# ADXL362WakeOnShake.net
KiCad netlist of a schematic drawn in EAGLE
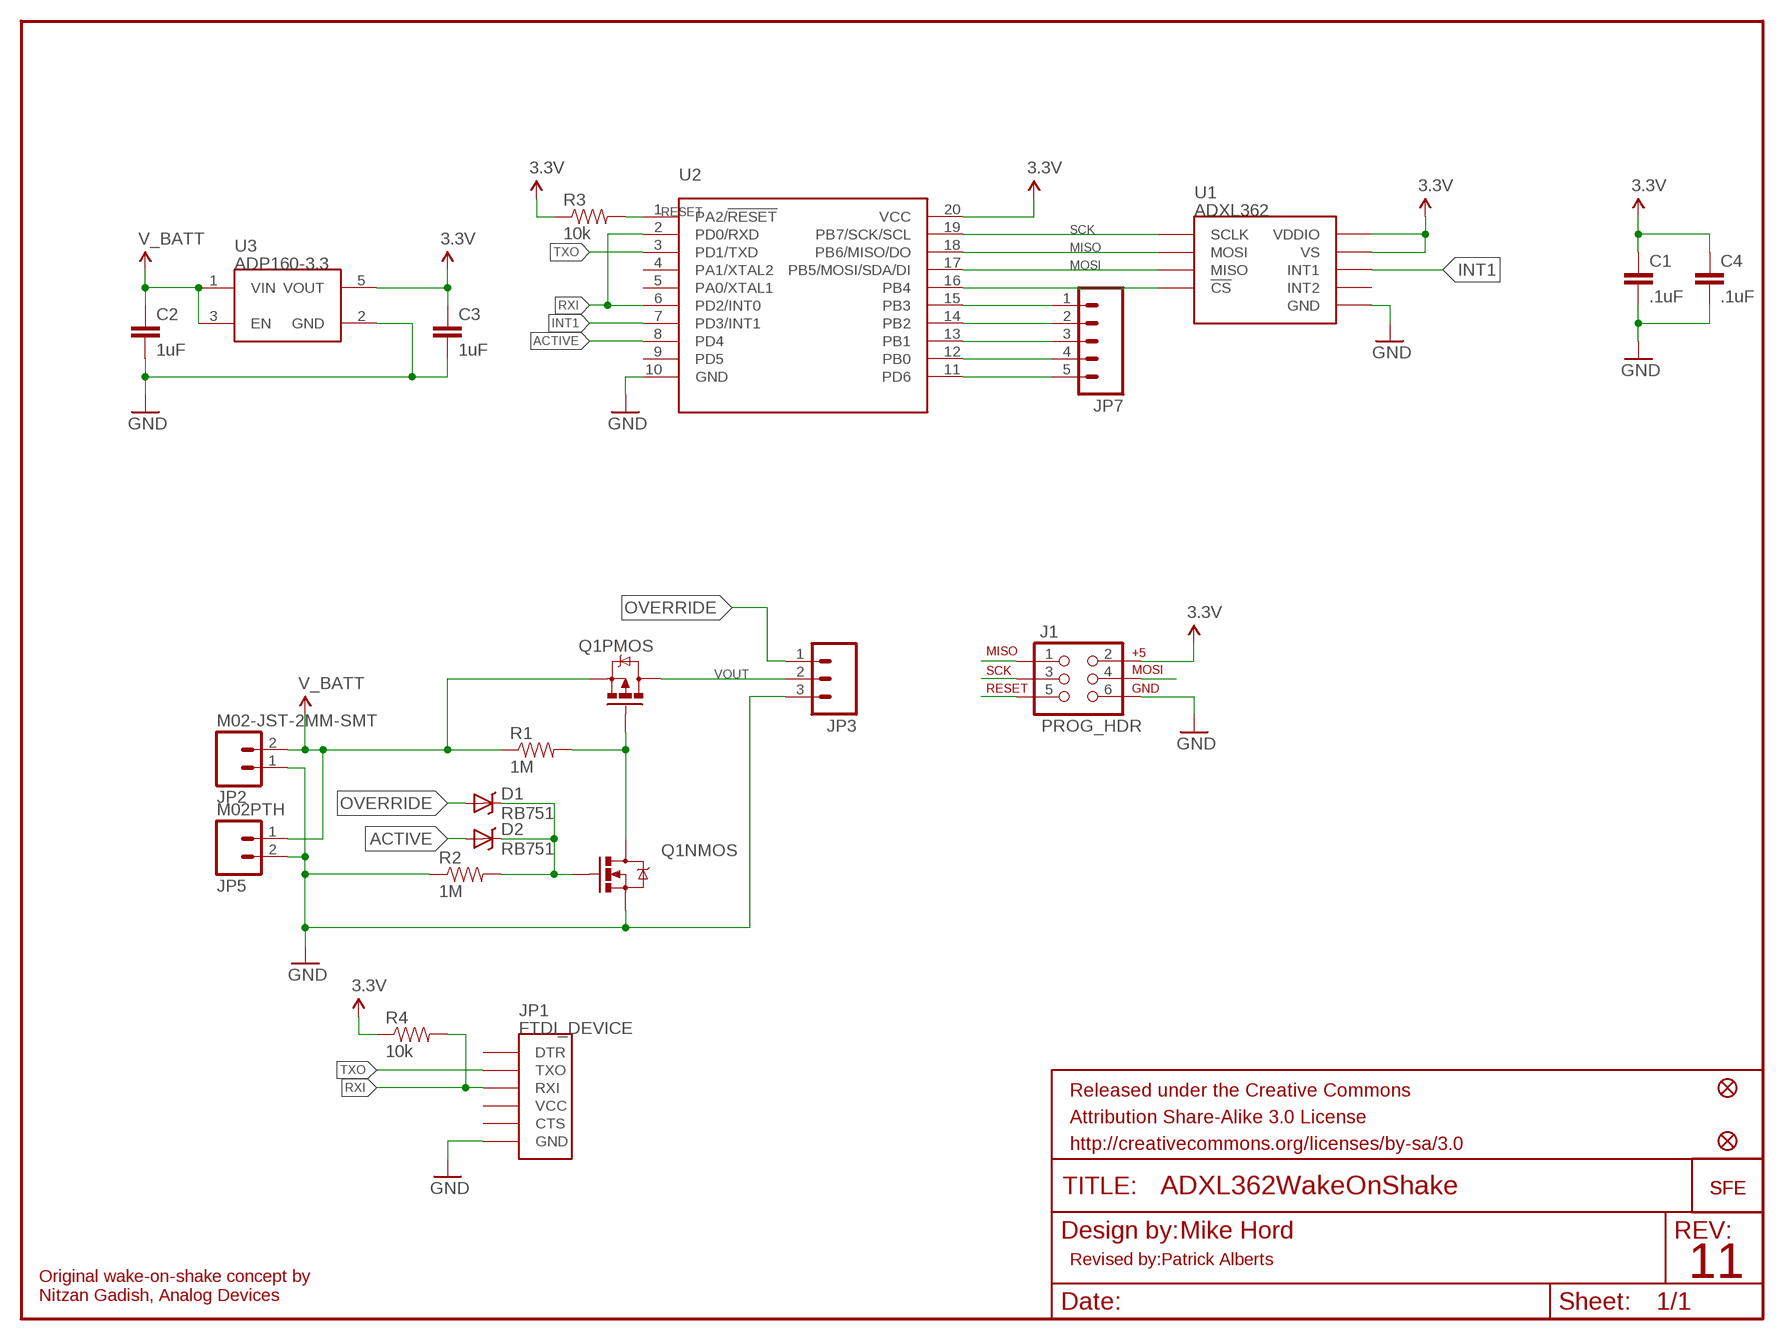
[diagram p0: schematic, sheet 1]

(export (version "E")
  (design (tool "Eeschema 10.0.6"))
  (components
    (comp (ref "C1")
      (value ".1uF")
      (footprint "eagle-import:0603-CAP")
      (fields (field (name "PROD_ID") "CAP-00810"))
      (libsource (lib "eagle-import") (part "0.1UF-25V(+80/-20%)(0603)"))
    )
    (comp (ref "C2")
      (value "1uF")
      (footprint "eagle-import:0603-CAP")
      (fields (field (name "PROD_ID") "CAP-00868"))
      (libsource (lib "eagle-import") (part "1.0UF-16V-10%(0603)"))
    )
    (comp (ref "C3")
      (value "1uF")
      (footprint "eagle-import:0603-CAP")
      (fields (field (name "PROD_ID") "CAP-00868"))
      (libsource (lib "eagle-import") (part "1.0UF-16V-10%(0603)"))
    )
    (comp (ref "C4")
      (value ".1uF")
      (footprint "eagle-import:0603-CAP")
      (fields (field (name "PROD_ID") "CAP-00810"))
      (libsource (lib "eagle-import") (part "0.1UF-25V(+80/-20%)(0603)"))
    )
    (comp (ref "D1")
      (value "RB751")
      (footprint "eagle-import:SOD-523")
      (fields (field (name "PROD_ID") "DIO-11018"))
      (libsource (lib "eagle-import") (part "RB751"))
    )
    (comp (ref "D2")
      (value "RB751")
      (footprint "eagle-import:SOD-523")
      (libsource (lib "eagle-import") (part "DIODE-SCHOTTKY"))
    )
    (comp (ref "FID1")
      (value "FIDUCIAL1X2")
      (footprint "eagle-import:FIDUCIAL-1X2")
      (libsource (lib "eagle-import") (part "FIDUCIAL1X2"))
    )
    (comp (ref "FID2")
      (value "FIDUCIAL1X2")
      (footprint "eagle-import:FIDUCIAL-1X2")
      (libsource (lib "eagle-import") (part "FIDUCIAL1X2"))
    )
    (comp (ref "FRAME1")
      (value "FRAME-LETTER")
      (footprint "eagle-import:CREATIVE_COMMONS")
      (libsource (lib "eagle-import") (part "FRAME-LETTER"))
    )
    (comp (ref "J1")
      (value "PROG_HDR")
      (footprint "eagle-import:2X3")
      (libsource (lib "eagle-import") (part "AVR_SPI_PRG_6PTH"))
    )
    (comp (ref "JP1")
      (value "FTDI_DEVICE")
      (footprint "eagle-import:FTDI_DEVICE_SIDE")
      (libsource (lib "eagle-import") (part "FTDI_DEVICE"))
    )
    (comp (ref "JP2")
      (value "M02-JST-2MM-SMT")
      (footprint "eagle-import:JST-2-SMD")
      (fields (field (name "PROD_ID") "CONN-08352"))
      (libsource (lib "eagle-import") (part "M02-JST-2MM-SMT"))
    )
    (comp (ref "JP3")
      (value "M03PTH")
      (footprint "eagle-import:1X03")
      (libsource (lib "eagle-import") (part "M03PTH"))
    )
    (comp (ref "JP4")
      (value "LOGO-SFENW2")
      (footprint "eagle-import:SFE-NEW-WEB")
      (libsource (lib "eagle-import") (part "LOGO-SFENW2"))
    )
    (comp (ref "JP5")
      (value "M02PTH")
      (footprint "eagle-import:1X02")
      (libsource (lib "eagle-import") (part "M02PTH"))
    )
    (comp (ref "JP6")
      (value "LOGO-SFENEW")
      (footprint "eagle-import:SFE-NEW-WEBLOGO")
      (libsource (lib "eagle-import") (part "LOGO-SFENEW"))
    )
    (comp (ref "JP7")
      (value "M05PTH")
      (footprint "eagle-import:1X05")
      (libsource (lib "eagle-import") (part "M05PTH"))
    )
    (comp (ref "Q1")
      (value "IRF7509")
      (footprint "eagle-import:MSOP8")
      (fields (field (name "PROD_ID") "TRANS-07913"))
      (libsource (lib "eagle-import") (part "IRF7509"))
    )
    (comp (ref "R1")
      (value "1M")
      (footprint "eagle-import:0603-RES")
      (fields (field (name "PROD_ID") "RES-07868"))
      (libsource (lib "eagle-import") (part "1MOHM1/10W1%(0603)"))
    )
    (comp (ref "R2")
      (value "1M")
      (footprint "eagle-import:0603-RES")
      (fields (field (name "PROD_ID") "RES-07868"))
      (libsource (lib "eagle-import") (part "1MOHM1/10W1%(0603)"))
    )
    (comp (ref "R3")
      (value "10k")
      (footprint "eagle-import:0603-RES")
      (fields (field (name "PROD_ID") "RES-00824"))
      (libsource (lib "eagle-import") (part "10K-1%RES-00824"))
    )
    (comp (ref "R4")
      (value "10k")
      (footprint "eagle-import:0603-RES")
      (fields (field (name "PROD_ID") "RES-00824"))
      (libsource (lib "eagle-import") (part "10K-1%RES-00824"))
    )
    (comp (ref "U1")
      (value "ADXL362")
      (footprint "eagle-import:ADXL362-1_1")
      (libsource (lib "eagle-import") (part "ADXL362ADXL362-1{colon}1"))
    )
    (comp (ref "U2")
      (value "ATTINY2313A")
      (footprint "eagle-import:SOP20W")
      (libsource (lib "eagle-import") (part "ATTINY2313A"))
    )
    (comp (ref "U3")
      (value "ADP160-3.3")
      (footprint "eagle-import:SOT23-5")
      (libsource (lib "eagle-import") (part "ADP160"))
    )
  )
  (nets
    (net (code "1") (name "/MISO") (class "Default")
      (node (ref "J1") (pin "1") (pinfunction "1_1") (pintype "passive"))
      (node (ref "U1") (pin "P$6") (pinfunction "MOSI_P$6") (pintype "bidirectional"))
      (node (ref "U2") (pin "18") (pinfunction "PB6/MISO/DO_18") (pintype "bidirectional"))
    )
    (net (code "2") (name "/MOSI") (class "Default")
      (node (ref "J1") (pin "4") (pinfunction "4_4") (pintype "passive"))
      (node (ref "U1") (pin "P$7") (pinfunction "MISO_P$7") (pintype "bidirectional"))
      (node (ref "U2") (pin "17") (pinfunction "PB5/MOSI/SDA/DI_17") (pintype "bidirectional"))
    )
    (net (code "3") (name "/RESET") (class "Default")
      (node (ref "J1") (pin "5") (pinfunction "5_5") (pintype "passive"))
      (node (ref "R3") (pin "2") (pinfunction "2_2") (pintype "passive"))
      (node (ref "U2") (pin "1") (pinfunction "PA2/~{RESET}_1") (pintype "bidirectional"))
    )
    (net (code "4") (name "/SCK") (class "Default")
      (node (ref "J1") (pin "3") (pinfunction "3_3") (pintype "passive"))
      (node (ref "U1") (pin "P$4") (pinfunction "SCLK_P$4") (pintype "bidirectional"))
      (node (ref "U2") (pin "19") (pinfunction "PB7/SCK/SCL_19") (pintype "bidirectional"))
    )
    (net (code "5") (name "/VOUT") (class "Default")
      (node (ref "JP3") (pin "2") (pinfunction "2_2") (pintype "passive"))
      (node (ref "Q1") (pin "5") (pinfunction "D_5") (pintype "passive"))
      (node (ref "Q1") (pin "6") (pinfunction "D_6") (pintype "passive"))
    )
    (net (code "6") (name "3.3V") (class "Default")
      (node (ref "C1") (pin "1") (pinfunction "1_1") (pintype "passive"))
      (node (ref "C3") (pin "1") (pinfunction "1_1") (pintype "passive"))
      (node (ref "C4") (pin "1") (pinfunction "1_1") (pintype "passive"))
      (node (ref "J1") (pin "2") (pinfunction "2_2") (pintype "passive"))
      (node (ref "R3") (pin "1") (pinfunction "1_1") (pintype "passive"))
      (node (ref "R4") (pin "1") (pinfunction "1_1") (pintype "passive"))
      (node (ref "U1") (pin "P$1") (pinfunction "VDDIO_P$1") (pintype "bidirectional"))
      (node (ref "U1") (pin "P$14") (pinfunction "VS_P$14") (pintype "bidirectional"))
      (node (ref "U2") (pin "20") (pinfunction "VCC_20") (pintype "bidirectional"))
      (node (ref "U3") (pin "5") (pinfunction "VOUT_5") (pintype "bidirectional"))
    )
    (net (code "7") (name "ACTIVE") (class "Default")
      (node (ref "D2") (pin "A") (pinfunction "A_A") (pintype "passive"))
      (node (ref "U2") (pin "8") (pinfunction "PD4_8") (pintype "bidirectional"))
    )
    (net (code "8") (name "GND") (class "Default")
      (node (ref "C1") (pin "2") (pinfunction "2_2") (pintype "passive"))
      (node (ref "C2") (pin "2") (pinfunction "2_2") (pintype "passive"))
      (node (ref "C3") (pin "2") (pinfunction "2_2") (pintype "passive"))
      (node (ref "C4") (pin "2") (pinfunction "2_2") (pintype "passive"))
      (node (ref "J1") (pin "6") (pinfunction "6_6") (pintype "passive"))
      (node (ref "JP1") (pin "P$6") (pinfunction "GND_P$6") (pintype "bidirectional"))
      (node (ref "JP2") (pin "1") (pinfunction "2_1") (pintype "passive"))
      (node (ref "JP3") (pin "3") (pinfunction "3_3") (pintype "passive"))
      (node (ref "JP5") (pin "2") (pinfunction "2_2") (pintype "passive"))
      (node (ref "Q1") (pin "1") (pinfunction "S_1") (pintype "passive"))
      (node (ref "R2") (pin "1") (pinfunction "1_1") (pintype "passive"))
      (node (ref "U1") (pin "P$12") (pinfunction "GND_P$12") (pintype "bidirectional"))
      (node (ref "U1") (pin "P$13") (pinfunction "GND_P$13") (pintype "bidirectional"))
      (node (ref "U1") (pin "P$16") (pinfunction "GND_P$16") (pintype "bidirectional"))
      (node (ref "U2") (pin "10") (pinfunction "GND_10") (pintype "bidirectional"))
      (node (ref "U3") (pin "2") (pinfunction "GND_2") (pintype "bidirectional"))
    )
    (net (code "9") (name "INT1") (class "Default")
      (node (ref "U1") (pin "P$11") (pinfunction "INT1_P$11") (pintype "bidirectional"))
      (node (ref "U2") (pin "7") (pinfunction "PD3/INT1_7") (pintype "bidirectional"))
    )
    (net (code "10") (name "Net-(Q1A-G)") (class "Default")
      (node (ref "D1") (pin "C") (pinfunction "C_C") (pintype "passive"))
      (node (ref "D2") (pin "C") (pinfunction "C_C") (pintype "passive"))
      (node (ref "Q1") (pin "2") (pinfunction "G_2") (pintype "passive"))
      (node (ref "R2") (pin "2") (pinfunction "2_2") (pintype "passive"))
    )
    (net (code "11") (name "Net-(Q1B-G)") (class "Default")
      (node (ref "Q1") (pin "4") (pinfunction "G_4") (pintype "passive"))
      (node (ref "Q1") (pin "7") (pinfunction "D_7") (pintype "passive"))
      (node (ref "Q1") (pin "8") (pinfunction "D_8") (pintype "passive"))
      (node (ref "R1") (pin "2") (pinfunction "2_2") (pintype "passive"))
    )
    (net (code "12") (name "Net-(U1-~{CS})") (class "Default")
      (node (ref "U1") (pin "P$8") (pinfunction "~{CS}_P$8") (pintype "bidirectional"))
      (node (ref "U2") (pin "16") (pinfunction "PB4_16") (pintype "bidirectional"))
    )
    (net (code "13") (name "Net-(U2-PB0)") (class "Default")
      (node (ref "JP7") (pin "4") (pinfunction "4_4") (pintype "passive"))
      (node (ref "U2") (pin "12") (pinfunction "PB0_12") (pintype "bidirectional"))
    )
    (net (code "14") (name "Net-(U2-PB1)") (class "Default")
      (node (ref "JP7") (pin "3") (pinfunction "3_3") (pintype "passive"))
      (node (ref "U2") (pin "13") (pinfunction "PB1_13") (pintype "bidirectional"))
    )
    (net (code "15") (name "Net-(U2-PB2)") (class "Default")
      (node (ref "JP7") (pin "2") (pinfunction "2_2") (pintype "passive"))
      (node (ref "U2") (pin "14") (pinfunction "PB2_14") (pintype "bidirectional"))
    )
    (net (code "16") (name "Net-(U2-PB3)") (class "Default")
      (node (ref "JP7") (pin "1") (pinfunction "1_1") (pintype "passive"))
      (node (ref "U2") (pin "15") (pinfunction "PB3_15") (pintype "bidirectional"))
    )
    (net (code "17") (name "Net-(U2-PD6)") (class "Default")
      (node (ref "JP7") (pin "5") (pinfunction "5_5") (pintype "passive"))
      (node (ref "U2") (pin "11") (pinfunction "PD6_11") (pintype "bidirectional"))
    )
    (net (code "18") (name "OVERRIDE") (class "Default")
      (node (ref "D1") (pin "A") (pinfunction "A_A") (pintype "passive"))
      (node (ref "JP3") (pin "1") (pinfunction "1_1") (pintype "passive"))
    )
    (net (code "19") (name "RXI") (class "Default")
      (node (ref "JP1") (pin "P$3") (pinfunction "RXI_P$3") (pintype "bidirectional"))
      (node (ref "R4") (pin "2") (pinfunction "2_2") (pintype "passive"))
      (node (ref "U2") (pin "2") (pinfunction "PD0/RXD_2") (pintype "bidirectional"))
      (node (ref "U2") (pin "6") (pinfunction "PD2/INT0_6") (pintype "bidirectional"))
    )
    (net (code "20") (name "TXO") (class "Default")
      (node (ref "JP1") (pin "P$2") (pinfunction "TXO_P$2") (pintype "bidirectional"))
      (node (ref "U2") (pin "3") (pinfunction "PD1/TXD_3") (pintype "bidirectional"))
    )
    (net (code "21") (name "V_BATT") (class "Default")
      (node (ref "C2") (pin "1") (pinfunction "1_1") (pintype "passive"))
      (node (ref "JP2") (pin "2") (pinfunction "1_2") (pintype "passive"))
      (node (ref "JP5") (pin "1") (pinfunction "1_1") (pintype "passive"))
      (node (ref "Q1") (pin "3") (pinfunction "S_3") (pintype "passive"))
      (node (ref "R1") (pin "1") (pinfunction "1_1") (pintype "passive"))
      (node (ref "U3") (pin "1") (pinfunction "VIN_1") (pintype "bidirectional"))
      (node (ref "U3") (pin "3") (pinfunction "EN_3") (pintype "bidirectional"))
    )
    (net (code "22") (name "unconnected-(JP1-CTS-PadP$5)") (class "Default")
      (node (ref "JP1") (pin "P$5") (pinfunction "CTS_P$5") (pintype "bidirectional"))
    )
    (net (code "23") (name "unconnected-(JP1-DTR-PadP$1)") (class "Default")
      (node (ref "JP1") (pin "P$1") (pinfunction "DTR_P$1") (pintype "bidirectional"))
    )
    (net (code "24") (name "unconnected-(JP1-VCC-PadP$4)") (class "Default")
      (node (ref "JP1") (pin "P$4") (pinfunction "VCC_P$4") (pintype "bidirectional"))
    )
    (net (code "25") (name "unconnected-(U1-INT2-PadP$9)") (class "Default")
      (node (ref "U1") (pin "P$9") (pinfunction "INT2_P$9") (pintype "bidirectional"))
    )
    (net (code "26") (name "unconnected-(U2-PA0{slash}XTAL1-Pad5)") (class "Default")
      (node (ref "U2") (pin "5") (pinfunction "PA0/XTAL1_5") (pintype "bidirectional"))
    )
    (net (code "27") (name "unconnected-(U2-PA1{slash}XTAL2-Pad4)") (class "Default")
      (node (ref "U2") (pin "4") (pinfunction "PA1/XTAL2_4") (pintype "bidirectional"))
    )
    (net (code "28") (name "unconnected-(U2-PD5-Pad9)") (class "Default")
      (node (ref "U2") (pin "9") (pinfunction "PD5_9") (pintype "bidirectional"))
    )
  )
)
